# durtest.net
KiCad netlist of a schematic drawn in EAGLE
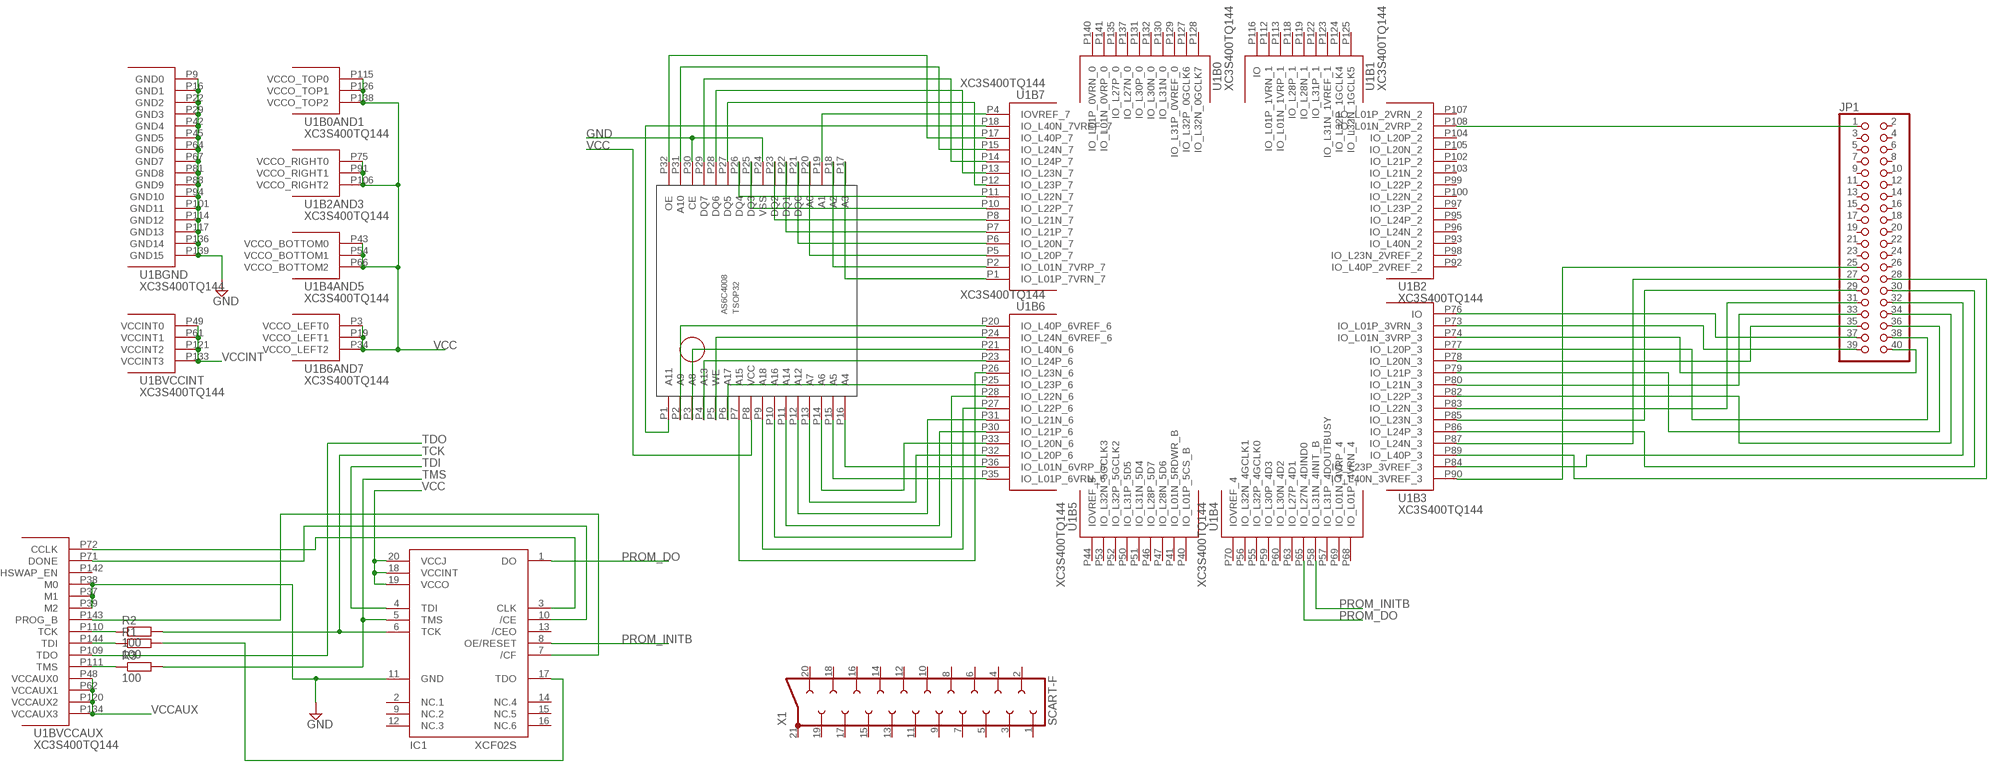
[diagram p0: schematic, sheet 1]

(export (version "E")
  (design (tool "Eeschema 10.0.6"))
  (components
    (comp (ref "IC1")
      (value "XCF02S")
      (footprint "eagle-import:VO20")
      (libsource (lib "eagle-import") (part "XCF02S"))
    )
    (comp (ref "JP1")
      (value "PINHD-2X20")
      (footprint "eagle-import:2X20")
      (libsource (lib "eagle-import") (part "PINHD-2X20"))
    )
    (comp (ref "R1")
      (value "100")
      (footprint "eagle-import:R0805")
      (libsource (lib "eagle-import") (part "R-EU_R0805"))
    )
    (comp (ref "R2")
      (value "100")
      (footprint "eagle-import:R0805")
      (libsource (lib "eagle-import") (part "R-EU_R0805"))
    )
    (comp (ref "R3")
      (value "100")
      (footprint "eagle-import:R0805")
      (libsource (lib "eagle-import") (part "R-EU_R0805"))
    )
    (comp (ref "U$1")
      (value "AS6C4008")
      (footprint "eagle-import:TSOP32")
      (libsource (lib "eagle-import") (part "AS6C4008"))
    )
    (comp (ref "U1")
      (value "XC3S400TQ144")
      (footprint "eagle-import:TQ144")
      (libsource (lib "eagle-import") (part "XC3S400TQ144"))
    )
    (comp (ref "X1")
      (value "SCART-F")
      (footprint "eagle-import:SCART-F")
      (libsource (lib "eagle-import") (part "SCART-F"))
    )
  )
  (nets
    (net (code "1") (name "/PROM_DO") (class "Default")
      (node (ref "IC1") (pin "1") (pinfunction "DO_1") (pintype "bidirectional"))
      (node (ref "U1") (pin "P65") (pinfunction "IO_L27N_4DIND0_P65") (pintype "bidirectional"))
    )
    (net (code "2") (name "/PROM_INITB") (class "Default")
      (node (ref "IC1") (pin "8") (pinfunction "OE/RESET_8") (pintype "bidirectional"))
      (node (ref "U1") (pin "P58") (pinfunction "IO_L31N_4INIT_B_P58") (pintype "bidirectional"))
    )
    (net (code "3") (name "/TCK") (class "Default")
      (node (ref "IC1") (pin "6") (pinfunction "TCK_6") (pintype "bidirectional"))
      (node (ref "R2") (pin "2") (pinfunction "2_2") (pintype "passive"))
    )
    (net (code "4") (name "/TDI") (class "Default")
      (node (ref "IC1") (pin "4") (pinfunction "TDI_4") (pintype "bidirectional"))
    )
    (net (code "5") (name "/TDO") (class "Default")
      (node (ref "U1") (pin "P109") (pinfunction "TDO_P109") (pintype "bidirectional"))
    )
    (net (code "6") (name "/TMS") (class "Default")
      (node (ref "IC1") (pin "5") (pinfunction "TMS_5") (pintype "bidirectional"))
      (node (ref "R3") (pin "2") (pinfunction "2_2") (pintype "passive"))
    )
    (net (code "7") (name "/VCC") (class "Default")
      (node (ref "IC1") (pin "18") (pinfunction "VCCINT_18") (pintype "bidirectional"))
      (node (ref "IC1") (pin "19") (pinfunction "VCCO_19") (pintype "bidirectional"))
      (node (ref "IC1") (pin "20") (pinfunction "VCCJ_20") (pintype "bidirectional"))
      (node (ref "U$1") (pin "P8") (pinfunction "VCC_P8") (pintype "bidirectional"))
      (node (ref "U1") (pin "P106") (pinfunction "VCCO_RIGHT2_P106") (pintype "passive"))
      (node (ref "U1") (pin "P115") (pinfunction "VCCO_TOP0_P115") (pintype "passive"))
      (node (ref "U1") (pin "P126") (pinfunction "VCCO_TOP1_P126") (pintype "passive"))
      (node (ref "U1") (pin "P138") (pinfunction "VCCO_TOP2_P138") (pintype "passive"))
      (node (ref "U1") (pin "P19") (pinfunction "VCCO_LEFT1_P19") (pintype "passive"))
      (node (ref "U1") (pin "P3") (pinfunction "VCCO_LEFT0_P3") (pintype "passive"))
      (node (ref "U1") (pin "P34") (pinfunction "VCCO_LEFT2_P34") (pintype "passive"))
      (node (ref "U1") (pin "P43") (pinfunction "VCCO_BOTTOM0_P43") (pintype "passive"))
      (node (ref "U1") (pin "P54") (pinfunction "VCCO_BOTTOM1_P54") (pintype "passive"))
      (node (ref "U1") (pin "P66") (pinfunction "VCCO_BOTTOM2_P66") (pintype "passive"))
      (node (ref "U1") (pin "P75") (pinfunction "VCCO_RIGHT0_P75") (pintype "passive"))
      (node (ref "U1") (pin "P91") (pinfunction "VCCO_RIGHT1_P91") (pintype "passive"))
    )
    (net (code "8") (name "/VCCAUX") (class "Default")
      (node (ref "U1") (pin "P120") (pinfunction "VCCAUX2_P120") (pintype "passive"))
      (node (ref "U1") (pin "P134") (pinfunction "VCCAUX3_P134") (pintype "passive"))
      (node (ref "U1") (pin "P48") (pinfunction "VCCAUX0_P48") (pintype "passive"))
      (node (ref "U1") (pin "P62") (pinfunction "VCCAUX1_P62") (pintype "passive"))
    )
    (net (code "9") (name "/VCCINT") (class "Default")
      (node (ref "U1") (pin "P121") (pinfunction "VCCINT2_P121") (pintype "passive"))
      (node (ref "U1") (pin "P133") (pinfunction "VCCINT3_P133") (pintype "passive"))
      (node (ref "U1") (pin "P49") (pinfunction "VCCINT0_P49") (pintype "passive"))
      (node (ref "U1") (pin "P61") (pinfunction "VCCINT1_P61") (pintype "passive"))
    )
    (net (code "10") (name "GND") (class "Default")
      (node (ref "IC1") (pin "11") (pinfunction "GND_11") (pintype "bidirectional"))
      (node (ref "U$1") (pin "P24") (pinfunction "VSS_P24") (pintype "bidirectional"))
      (node (ref "U$1") (pin "P30") (pinfunction "CE_P30") (pintype "bidirectional"))
      (node (ref "U1") (pin "P101") (pinfunction "GND11_P101") (pintype "passive"))
      (node (ref "U1") (pin "P114") (pinfunction "GND12_P114") (pintype "passive"))
      (node (ref "U1") (pin "P117") (pinfunction "GND13_P117") (pintype "passive"))
      (node (ref "U1") (pin "P136") (pinfunction "GND14_P136") (pintype "passive"))
      (node (ref "U1") (pin "P139") (pinfunction "GND15_P139") (pintype "passive"))
      (node (ref "U1") (pin "P16") (pinfunction "GND1_P16") (pintype "passive"))
      (node (ref "U1") (pin "P22") (pinfunction "GND2_P22") (pintype "passive"))
      (node (ref "U1") (pin "P29") (pinfunction "GND3_P29") (pintype "passive"))
      (node (ref "U1") (pin "P37") (pinfunction "M1_P37") (pintype "bidirectional"))
      (node (ref "U1") (pin "P38") (pinfunction "M0_P38") (pintype "bidirectional"))
      (node (ref "U1") (pin "P39") (pinfunction "M2_P39") (pintype "bidirectional"))
      (node (ref "U1") (pin "P42") (pinfunction "GND4_P42") (pintype "passive"))
      (node (ref "U1") (pin "P45") (pinfunction "GND5_P45") (pintype "passive"))
      (node (ref "U1") (pin "P64") (pinfunction "GND6_P64") (pintype "passive"))
      (node (ref "U1") (pin "P67") (pinfunction "GND7_P67") (pintype "passive"))
      (node (ref "U1") (pin "P81") (pinfunction "GND8_P81") (pintype "passive"))
      (node (ref "U1") (pin "P88") (pinfunction "GND9_P88") (pintype "passive"))
      (node (ref "U1") (pin "P9") (pinfunction "GND0_P9") (pintype "passive"))
      (node (ref "U1") (pin "P94") (pinfunction "GND10_P94") (pintype "passive"))
    )
    (net (code "11") (name "Net-(IC1-CLK)") (class "Default")
      (node (ref "IC1") (pin "3") (pinfunction "CLK_3") (pintype "bidirectional"))
      (node (ref "U1") (pin "P72") (pinfunction "CCLK_P72") (pintype "bidirectional"))
    )
    (net (code "12") (name "Net-(IC1-TDO)") (class "Default")
      (node (ref "IC1") (pin "17") (pinfunction "TDO_17") (pintype "bidirectional"))
      (node (ref "R1") (pin "2") (pinfunction "2_2") (pintype "passive"))
    )
    (net (code "13") (name "Net-(IC1-{slash}CE)") (class "Default")
      (node (ref "IC1") (pin "10") (pinfunction "/CE_10") (pintype "bidirectional"))
      (node (ref "U1") (pin "P71") (pinfunction "DONE_P71") (pintype "bidirectional"))
    )
    (net (code "14") (name "Net-(IC1-{slash}CF)") (class "Default")
      (node (ref "IC1") (pin "7") (pinfunction "/CF_7") (pintype "bidirectional"))
      (node (ref "U1") (pin "P143") (pinfunction "PROG_B_P143") (pintype "bidirectional"))
    )
    (net (code "15") (name "Net-(U$1-A0)") (class "Default")
      (node (ref "U$1") (pin "P20") (pinfunction "A0_P20") (pintype "bidirectional"))
      (node (ref "U1") (pin "P5") (pinfunction "IO_L20P_7_P5") (pintype "bidirectional"))
    )
    (net (code "16") (name "Net-(U$1-A1)") (class "Default")
      (node (ref "U$1") (pin "P19") (pinfunction "A1_P19") (pintype "bidirectional"))
      (node (ref "U1") (pin "P4") (pinfunction "IOVREF_7_P4") (pintype "bidirectional"))
    )
    (net (code "17") (name "Net-(U$1-A2)") (class "Default")
      (node (ref "U$1") (pin "P18") (pinfunction "A2_P18") (pintype "bidirectional"))
      (node (ref "U1") (pin "P2") (pinfunction "IO_L01N_7VRP_7_P2") (pintype "bidirectional"))
    )
    (net (code "18") (name "Net-(U$1-A3)") (class "Default")
      (node (ref "U$1") (pin "P17") (pinfunction "A3_P17") (pintype "bidirectional"))
      (node (ref "U1") (pin "P1") (pinfunction "IO_L01P_7VRN_7_P1") (pintype "bidirectional"))
    )
    (net (code "19") (name "Net-(U$1-A4)") (class "Default")
      (node (ref "U$1") (pin "P16") (pinfunction "A4_P16") (pintype "bidirectional"))
      (node (ref "U1") (pin "P36") (pinfunction "IO_L01N_6VRP_6_P36") (pintype "bidirectional"))
    )
    (net (code "20") (name "Net-(U$1-A5)") (class "Default")
      (node (ref "U$1") (pin "P15") (pinfunction "A5_P15") (pintype "bidirectional"))
      (node (ref "U1") (pin "P35") (pinfunction "IO_L01P_6VRN_6_P35") (pintype "bidirectional"))
    )
    (net (code "21") (name "Net-(U$1-A6)") (class "Default")
      (node (ref "U$1") (pin "P14") (pinfunction "A6_P14") (pintype "bidirectional"))
      (node (ref "U1") (pin "P33") (pinfunction "IO_L20N_6_P33") (pintype "bidirectional"))
    )
    (net (code "22") (name "Net-(U$1-A7)") (class "Default")
      (node (ref "U$1") (pin "P13") (pinfunction "A7_P13") (pintype "bidirectional"))
      (node (ref "U1") (pin "P32") (pinfunction "IO_L20P_6_P32") (pintype "bidirectional"))
    )
    (net (code "23") (name "Net-(U$1-A8)") (class "Default")
      (node (ref "U$1") (pin "P3") (pinfunction "A8_P3") (pintype "bidirectional"))
      (node (ref "U1") (pin "P21") (pinfunction "IO_L40N_6_P21") (pintype "bidirectional"))
    )
    (net (code "24") (name "Net-(U$1-A9)") (class "Default")
      (node (ref "U$1") (pin "P2") (pinfunction "A9_P2") (pintype "bidirectional"))
      (node (ref "U1") (pin "P20") (pinfunction "IO_L40P_6VREF_6_P20") (pintype "bidirectional"))
    )
    (net (code "25") (name "Net-(U$1-A10)") (class "Default")
      (node (ref "U$1") (pin "P31") (pinfunction "A10_P31") (pintype "bidirectional"))
      (node (ref "U1") (pin "P15") (pinfunction "IO_L24N_7_P15") (pintype "bidirectional"))
    )
    (net (code "26") (name "Net-(U$1-A11)") (class "Default")
      (node (ref "U$1") (pin "P1") (pinfunction "A11_P1") (pintype "bidirectional"))
      (node (ref "U1") (pin "P18") (pinfunction "IO_L40N_7VREF_7_P18") (pintype "bidirectional"))
    )
    (net (code "27") (name "Net-(U$1-A12)") (class "Default")
      (node (ref "U$1") (pin "P12") (pinfunction "A12_P12") (pintype "bidirectional"))
      (node (ref "U1") (pin "P31") (pinfunction "IO_L21N_6_P31") (pintype "bidirectional"))
    )
    (net (code "28") (name "Net-(U$1-A13)") (class "Default")
      (node (ref "U$1") (pin "P4") (pinfunction "A13_P4") (pintype "bidirectional"))
      (node (ref "U1") (pin "P23") (pinfunction "IO_L24P_6_P23") (pintype "bidirectional"))
    )
    (net (code "29") (name "Net-(U$1-A14)") (class "Default")
      (node (ref "U$1") (pin "P11") (pinfunction "A14_P11") (pintype "bidirectional"))
      (node (ref "U1") (pin "P30") (pinfunction "IO_L21P_6_P30") (pintype "bidirectional"))
    )
    (net (code "30") (name "Net-(U$1-A15)") (class "Default")
      (node (ref "U$1") (pin "P7") (pinfunction "A15_P7") (pintype "bidirectional"))
      (node (ref "U1") (pin "P26") (pinfunction "IO_L23N_6_P26") (pintype "bidirectional"))
    )
    (net (code "31") (name "Net-(U$1-A16)") (class "Default")
      (node (ref "U$1") (pin "P10") (pinfunction "A16_P10") (pintype "bidirectional"))
      (node (ref "U1") (pin "P28") (pinfunction "IO_L22N_6_P28") (pintype "bidirectional"))
    )
    (net (code "32") (name "Net-(U$1-A17)") (class "Default")
      (node (ref "U$1") (pin "P6") (pinfunction "A17_P6") (pintype "bidirectional"))
      (node (ref "U1") (pin "P25") (pinfunction "IO_L23P_6_P25") (pintype "bidirectional"))
    )
    (net (code "33") (name "Net-(U$1-A18)") (class "Default")
      (node (ref "U$1") (pin "P9") (pinfunction "A18_P9") (pintype "bidirectional"))
      (node (ref "U1") (pin "P27") (pinfunction "IO_L22P_6_P27") (pintype "bidirectional"))
    )
    (net (code "34") (name "Net-(U$1-DQ0)") (class "Default")
      (node (ref "U$1") (pin "P21") (pinfunction "DQ0_P21") (pintype "bidirectional"))
      (node (ref "U1") (pin "P6") (pinfunction "IO_L20N_7_P6") (pintype "bidirectional"))
    )
    (net (code "35") (name "Net-(U$1-DQ1)") (class "Default")
      (node (ref "U$1") (pin "P22") (pinfunction "DQ1_P22") (pintype "bidirectional"))
      (node (ref "U1") (pin "P7") (pinfunction "IO_L21P_7_P7") (pintype "bidirectional"))
    )
    (net (code "36") (name "Net-(U$1-DQ2)") (class "Default")
      (node (ref "U$1") (pin "P23") (pinfunction "DQ2_P23") (pintype "bidirectional"))
      (node (ref "U1") (pin "P8") (pinfunction "IO_L21N_7_P8") (pintype "bidirectional"))
    )
    (net (code "37") (name "Net-(U$1-DQ3)") (class "Default")
      (node (ref "U$1") (pin "P25") (pinfunction "DQ3_P25") (pintype "bidirectional"))
      (node (ref "U1") (pin "P10") (pinfunction "IO_L22P_7_P10") (pintype "bidirectional"))
    )
    (net (code "38") (name "Net-(U$1-DQ4)") (class "Default")
      (node (ref "U$1") (pin "P26") (pinfunction "DQ4_P26") (pintype "bidirectional"))
      (node (ref "U1") (pin "P11") (pinfunction "IO_L22N_7_P11") (pintype "bidirectional"))
    )
    (net (code "39") (name "Net-(U$1-DQ5)") (class "Default")
      (node (ref "U$1") (pin "P27") (pinfunction "DQ5_P27") (pintype "bidirectional"))
      (node (ref "U1") (pin "P12") (pinfunction "IO_L23P_7_P12") (pintype "bidirectional"))
    )
    (net (code "40") (name "Net-(U$1-DQ6)") (class "Default")
      (node (ref "U$1") (pin "P28") (pinfunction "DQ6_P28") (pintype "bidirectional"))
      (node (ref "U1") (pin "P13") (pinfunction "IO_L23N_7_P13") (pintype "bidirectional"))
    )
    (net (code "41") (name "Net-(U$1-DQ7)") (class "Default")
      (node (ref "U$1") (pin "P29") (pinfunction "DQ7_P29") (pintype "bidirectional"))
      (node (ref "U1") (pin "P14") (pinfunction "IO_L24P_7_P14") (pintype "bidirectional"))
    )
    (net (code "42") (name "Net-(U$1-OE)") (class "Default")
      (node (ref "U$1") (pin "P32") (pinfunction "OE_P32") (pintype "bidirectional"))
      (node (ref "U1") (pin "P17") (pinfunction "IO_L40P_7_P17") (pintype "bidirectional"))
    )
    (net (code "43") (name "Net-(U$1-WE)") (class "Default")
      (node (ref "U$1") (pin "P5") (pinfunction "WE_P5") (pintype "bidirectional"))
      (node (ref "U1") (pin "P24") (pinfunction "IO_L24N_6VREF_6_P24") (pintype "bidirectional"))
    )
    (net (code "44") (name "Net-(U1D-IO_L01N_2VRP_2)") (class "Default")
      (node (ref "JP1") (pin "1") (pinfunction "1_1") (pintype "passive"))
      (node (ref "U1") (pin "P108") (pinfunction "IO_L01N_2VRP_2_P108") (pintype "bidirectional"))
    )
    (net (code "45") (name "Net-(U1F-IO)") (class "Default")
      (node (ref "JP1") (pin "37") (pinfunction "37_37") (pintype "passive"))
      (node (ref "U1") (pin "P76") (pinfunction "IO_P76") (pintype "bidirectional"))
    )
    (net (code "46") (name "Net-(U1F-IO_L01N_3VRP_3)") (class "Default")
      (node (ref "JP1") (pin "40") (pinfunction "40_40") (pintype "passive"))
      (node (ref "U1") (pin "P74") (pinfunction "IO_L01N_3VRP_3_P74") (pintype "bidirectional"))
    )
    (net (code "47") (name "Net-(U1F-IO_L01P_3VRN_3)") (class "Default")
      (node (ref "JP1") (pin "39") (pinfunction "39_39") (pintype "passive"))
      (node (ref "U1") (pin "P73") (pinfunction "IO_L01P_3VRN_3_P73") (pintype "bidirectional"))
    )
    (net (code "48") (name "Net-(U1F-IO_L20N_3)") (class "Default")
      (node (ref "JP1") (pin "35") (pinfunction "35_35") (pintype "passive"))
      (node (ref "U1") (pin "P78") (pinfunction "IO_L20N_3_P78") (pintype "bidirectional"))
    )
    (net (code "49") (name "Net-(U1F-IO_L20P_3)") (class "Default")
      (node (ref "JP1") (pin "38") (pinfunction "38_38") (pintype "passive"))
      (node (ref "U1") (pin "P77") (pinfunction "IO_L20P_3_P77") (pintype "bidirectional"))
    )
    (net (code "50") (name "Net-(U1F-IO_L21N_3)") (class "Default")
      (node (ref "JP1") (pin "33") (pinfunction "33_33") (pintype "passive"))
      (node (ref "U1") (pin "P80") (pinfunction "IO_L21N_3_P80") (pintype "bidirectional"))
    )
    (net (code "51") (name "Net-(U1F-IO_L21P_3)") (class "Default")
      (node (ref "JP1") (pin "36") (pinfunction "36_36") (pintype "passive"))
      (node (ref "U1") (pin "P79") (pinfunction "IO_L21P_3_P79") (pintype "bidirectional"))
    )
    (net (code "52") (name "Net-(U1F-IO_L22N_3)") (class "Default")
      (node (ref "JP1") (pin "31") (pinfunction "31_31") (pintype "passive"))
      (node (ref "U1") (pin "P83") (pinfunction "IO_L22N_3_P83") (pintype "bidirectional"))
    )
    (net (code "53") (name "Net-(U1F-IO_L22P_3)") (class "Default")
      (node (ref "JP1") (pin "34") (pinfunction "34_34") (pintype "passive"))
      (node (ref "U1") (pin "P82") (pinfunction "IO_L22P_3_P82") (pintype "bidirectional"))
    )
    (net (code "54") (name "Net-(U1F-IO_L23N_3)") (class "Default")
      (node (ref "JP1") (pin "29") (pinfunction "29_29") (pintype "passive"))
      (node (ref "U1") (pin "P85") (pinfunction "IO_L23N_3_P85") (pintype "bidirectional"))
    )
    (net (code "55") (name "Net-(U1F-IO_L23P_3VREF_3)") (class "Default")
      (node (ref "JP1") (pin "32") (pinfunction "32_32") (pintype "passive"))
      (node (ref "U1") (pin "P84") (pinfunction "IO_L23P_3VREF_3_P84") (pintype "bidirectional"))
    )
    (net (code "56") (name "Net-(U1F-IO_L24N_3)") (class "Default")
      (node (ref "JP1") (pin "27") (pinfunction "27_27") (pintype "passive"))
      (node (ref "U1") (pin "P87") (pinfunction "IO_L24N_3_P87") (pintype "bidirectional"))
    )
    (net (code "57") (name "Net-(U1F-IO_L24P_3)") (class "Default")
      (node (ref "JP1") (pin "30") (pinfunction "30_30") (pintype "passive"))
      (node (ref "U1") (pin "P86") (pinfunction "IO_L24P_3_P86") (pintype "bidirectional"))
    )
    (net (code "58") (name "Net-(U1F-IO_L40N_3VREF_3)") (class "Default")
      (node (ref "JP1") (pin "25") (pinfunction "25_25") (pintype "passive"))
      (node (ref "U1") (pin "P90") (pinfunction "IO_L40N_3VREF_3_P90") (pintype "bidirectional"))
    )
    (net (code "59") (name "Net-(U1F-IO_L40P_3)") (class "Default")
      (node (ref "JP1") (pin "28") (pinfunction "28_28") (pintype "passive"))
      (node (ref "U1") (pin "P89") (pinfunction "IO_L40P_3_P89") (pintype "bidirectional"))
    )
    (net (code "60") (name "Net-(U1N-TCK)") (class "Default")
      (node (ref "R2") (pin "1") (pinfunction "1_1") (pintype "passive"))
      (node (ref "U1") (pin "P110") (pinfunction "TCK_P110") (pintype "bidirectional"))
    )
    (net (code "61") (name "Net-(U1N-TDI)") (class "Default")
      (node (ref "R1") (pin "1") (pinfunction "1_1") (pintype "passive"))
      (node (ref "U1") (pin "P144") (pinfunction "TDI_P144") (pintype "bidirectional"))
    )
    (net (code "62") (name "Net-(U1N-TMS)") (class "Default")
      (node (ref "R3") (pin "1") (pinfunction "1_1") (pintype "passive"))
      (node (ref "U1") (pin "P111") (pinfunction "TMS_P111") (pintype "bidirectional"))
    )
    (net (code "63") (name "unconnected-(IC1-NC.1-Pad2)") (class "Default")
      (node (ref "IC1") (pin "2") (pinfunction "NC.1_2") (pintype "bidirectional"))
    )
    (net (code "64") (name "unconnected-(IC1-NC.2-Pad9)") (class "Default")
      (node (ref "IC1") (pin "9") (pinfunction "NC.2_9") (pintype "bidirectional"))
    )
    (net (code "65") (name "unconnected-(IC1-NC.3-Pad12)") (class "Default")
      (node (ref "IC1") (pin "12") (pinfunction "NC.3_12") (pintype "bidirectional"))
    )
    (net (code "66") (name "unconnected-(IC1-NC.4-Pad14)") (class "Default")
      (node (ref "IC1") (pin "14") (pinfunction "NC.4_14") (pintype "bidirectional"))
    )
    (net (code "67") (name "unconnected-(IC1-NC.5-Pad15)") (class "Default")
      (node (ref "IC1") (pin "15") (pinfunction "NC.5_15") (pintype "bidirectional"))
    )
    (net (code "68") (name "unconnected-(IC1-NC.6-Pad16)") (class "Default")
      (node (ref "IC1") (pin "16") (pinfunction "NC.6_16") (pintype "bidirectional"))
    )
    (net (code "69") (name "unconnected-(IC1-{slash}CEO-Pad13)") (class "Default")
      (node (ref "IC1") (pin "13") (pinfunction "/CEO_13") (pintype "bidirectional"))
    )
    (net (code "70") (name "unconnected-(JP1-Pad2)") (class "Default")
      (node (ref "JP1") (pin "2") (pinfunction "2_2") (pintype "passive"))
    )
    (net (code "71") (name "unconnected-(JP1-Pad3)") (class "Default")
      (node (ref "JP1") (pin "3") (pinfunction "3_3") (pintype "passive"))
    )
    (net (code "72") (name "unconnected-(JP1-Pad4)") (class "Default")
      (node (ref "JP1") (pin "4") (pinfunction "4_4") (pintype "passive"))
    )
    (net (code "73") (name "unconnected-(JP1-Pad5)") (class "Default")
      (node (ref "JP1") (pin "5") (pinfunction "5_5") (pintype "passive"))
    )
    (net (code "74") (name "unconnected-(JP1-Pad6)") (class "Default")
      (node (ref "JP1") (pin "6") (pinfunction "6_6") (pintype "passive"))
    )
    (net (code "75") (name "unconnected-(JP1-Pad7)") (class "Default")
      (node (ref "JP1") (pin "7") (pinfunction "7_7") (pintype "passive"))
    )
    (net (code "76") (name "unconnected-(JP1-Pad8)") (class "Default")
      (node (ref "JP1") (pin "8") (pinfunction "8_8") (pintype "passive"))
    )
    (net (code "77") (name "unconnected-(JP1-Pad9)") (class "Default")
      (node (ref "JP1") (pin "9") (pinfunction "9_9") (pintype "passive"))
    )
    (net (code "78") (name "unconnected-(JP1-Pad10)") (class "Default")
      (node (ref "JP1") (pin "10") (pinfunction "10_10") (pintype "passive"))
    )
    (net (code "79") (name "unconnected-(JP1-Pad11)") (class "Default")
      (node (ref "JP1") (pin "11") (pinfunction "11_11") (pintype "passive"))
    )
    (net (code "80") (name "unconnected-(JP1-Pad12)") (class "Default")
      (node (ref "JP1") (pin "12") (pinfunction "12_12") (pintype "passive"))
    )
    (net (code "81") (name "unconnected-(JP1-Pad13)") (class "Default")
      (node (ref "JP1") (pin "13") (pinfunction "13_13") (pintype "passive"))
    )
    (net (code "82") (name "unconnected-(JP1-Pad14)") (class "Default")
      (node (ref "JP1") (pin "14") (pinfunction "14_14") (pintype "passive"))
    )
    (net (code "83") (name "unconnected-(JP1-Pad15)") (class "Default")
      (node (ref "JP1") (pin "15") (pinfunction "15_15") (pintype "passive"))
    )
    (net (code "84") (name "unconnected-(JP1-Pad16)") (class "Default")
      (node (ref "JP1") (pin "16") (pinfunction "16_16") (pintype "passive"))
    )
    (net (code "85") (name "unconnected-(JP1-Pad17)") (class "Default")
      (node (ref "JP1") (pin "17") (pinfunction "17_17") (pintype "passive"))
    )
    (net (code "86") (name "unconnected-(JP1-Pad18)") (class "Default")
      (node (ref "JP1") (pin "18") (pinfunction "18_18") (pintype "passive"))
    )
    (net (code "87") (name "unconnected-(JP1-Pad19)") (class "Default")
      (node (ref "JP1") (pin "19") (pinfunction "19_19") (pintype "passive"))
    )
    (net (code "88") (name "unconnected-(JP1-Pad20)") (class "Default")
      (node (ref "JP1") (pin "20") (pinfunction "20_20") (pintype "passive"))
    )
    (net (code "89") (name "unconnected-(JP1-Pad21)") (class "Default")
      (node (ref "JP1") (pin "21") (pinfunction "21_21") (pintype "passive"))
    )
    (net (code "90") (name "unconnected-(JP1-Pad22)") (class "Default")
      (node (ref "JP1") (pin "22") (pinfunction "22_22") (pintype "passive"))
    )
    (net (code "91") (name "unconnected-(JP1-Pad23)") (class "Default")
      (node (ref "JP1") (pin "23") (pinfunction "23_23") (pintype "passive"))
    )
    (net (code "92") (name "unconnected-(JP1-Pad24)") (class "Default")
      (node (ref "JP1") (pin "24") (pinfunction "24_24") (pintype "passive"))
    )
    (net (code "93") (name "unconnected-(JP1-Pad26)") (class "Default")
      (node (ref "JP1") (pin "26") (pinfunction "26_26") (pintype "passive"))
    )
    (net (code "94") (name "unconnected-(U1A-IO_L01N_0VRP_0-PadP141)") (class "Default")
      (node (ref "U1") (pin "P141") (pinfunction "IO_L01N_0VRP_0_P141") (pintype "bidirectional"))
    )
    (net (code "95") (name "unconnected-(U1A-IO_L01P_0VRN_0-PadP140)") (class "Default")
      (node (ref "U1") (pin "P140") (pinfunction "IO_L01P_0VRN_0_P140") (pintype "bidirectional"))
    )
    (net (code "96") (name "unconnected-(U1A-IO_L27N_0-PadP137)") (class "Default")
      (node (ref "U1") (pin "P137") (pinfunction "IO_L27N_0_P137") (pintype "bidirectional"))
    )
    (net (code "97") (name "unconnected-(U1A-IO_L27P_0-PadP135)") (class "Default")
      (node (ref "U1") (pin "P135") (pinfunction "IO_L27P_0_P135") (pintype "bidirectional"))
    )
    (net (code "98") (name "unconnected-(U1A-IO_L30N_0-PadP132)") (class "Default")
      (node (ref "U1") (pin "P132") (pinfunction "IO_L30N_0_P132") (pintype "bidirectional"))
    )
    (net (code "99") (name "unconnected-(U1A-IO_L30P_0-PadP131)") (class "Default")
      (node (ref "U1") (pin "P131") (pinfunction "IO_L30P_0_P131") (pintype "bidirectional"))
    )
    (net (code "100") (name "unconnected-(U1A-IO_L31N_0-PadP130)") (class "Default")
      (node (ref "U1") (pin "P130") (pinfunction "IO_L31N_0_P130") (pintype "bidirectional"))
    )
    (net (code "101") (name "unconnected-(U1A-IO_L31P_0VREF_0-PadP129)") (class "Default")
      (node (ref "U1") (pin "P129") (pinfunction "IO_L31P_0VREF_0_P129") (pintype "bidirectional"))
    )
    (net (code "102") (name "unconnected-(U1A-IO_L32N_0GCLK7-PadP128)") (class "Default")
      (node (ref "U1") (pin "P128") (pinfunction "IO_L32N_0GCLK7_P128") (pintype "bidirectional"))
    )
    (net (code "103") (name "unconnected-(U1A-IO_L32P_0GCLK6-PadP127)") (class "Default")
      (node (ref "U1") (pin "P127") (pinfunction "IO_L32P_0GCLK6_P127") (pintype "bidirectional"))
    )
    (net (code "104") (name "unconnected-(U1C-IO-PadP116)") (class "Default")
      (node (ref "U1") (pin "P116") (pinfunction "IO_P116") (pintype "bidirectional"))
    )
    (net (code "105") (name "unconnected-(U1C-IO_L01N_1VRP_1-PadP113)") (class "Default")
      (node (ref "U1") (pin "P113") (pinfunction "IO_L01N_1VRP_1_P113") (pintype "bidirectional"))
    )
    (net (code "106") (name "unconnected-(U1C-IO_L01P_1VRN_1-PadP112)") (class "Default")
      (node (ref "U1") (pin "P112") (pinfunction "IO_L01P_1VRN_1_P112") (pintype "bidirectional"))
    )
    (net (code "107") (name "unconnected-(U1C-IO_L28N_1-PadP119)") (class "Default")
      (node (ref "U1") (pin "P119") (pinfunction "IO_L28N_1_P119") (pintype "bidirectional"))
    )
    (net (code "108") (name "unconnected-(U1C-IO_L28P_1-PadP118)") (class "Default")
      (node (ref "U1") (pin "P118") (pinfunction "IO_L28P_1_P118") (pintype "bidirectional"))
    )
    (net (code "109") (name "unconnected-(U1C-IO_L31N_1VREF_1-PadP123)") (class "Default")
      (node (ref "U1") (pin "P123") (pinfunction "IO_L31N_1VREF_1_P123") (pintype "bidirectional"))
    )
    (net (code "110") (name "unconnected-(U1C-IO_L31P_1-PadP122)") (class "Default")
      (node (ref "U1") (pin "P122") (pinfunction "IO_L31P_1_P122") (pintype "bidirectional"))
    )
    (net (code "111") (name "unconnected-(U1C-IO_L32N_1GCLK5-PadP125)") (class "Default")
      (node (ref "U1") (pin "P125") (pinfunction "IO_L32N_1GCLK5_P125") (pintype "bidirectional"))
    )
    (net (code "112") (name "unconnected-(U1C-IO_L32P_1GCLK4-PadP124)") (class "Default")
      (node (ref "U1") (pin "P124") (pinfunction "IO_L32P_1GCLK4_P124") (pintype "bidirectional"))
    )
    (net (code "113") (name "unconnected-(U1D-IO_L01P_2VRN_2-PadP107)") (class "Default")
      (node (ref "U1") (pin "P107") (pinfunction "IO_L01P_2VRN_2_P107") (pintype "bidirectional"))
    )
    (net (code "114") (name "unconnected-(U1D-IO_L20N_2-PadP105)") (class "Default")
      (node (ref "U1") (pin "P105") (pinfunction "IO_L20N_2_P105") (pintype "bidirectional"))
    )
    (net (code "115") (name "unconnected-(U1D-IO_L20P_2-PadP104)") (class "Default")
      (node (ref "U1") (pin "P104") (pinfunction "IO_L20P_2_P104") (pintype "bidirectional"))
    )
    (net (code "116") (name "unconnected-(U1D-IO_L21N_2-PadP103)") (class "Default")
      (node (ref "U1") (pin "P103") (pinfunction "IO_L21N_2_P103") (pintype "bidirectional"))
    )
    (net (code "117") (name "unconnected-(U1D-IO_L21P_2-PadP102)") (class "Default")
      (node (ref "U1") (pin "P102") (pinfunction "IO_L21P_2_P102") (pintype "bidirectional"))
    )
    (net (code "118") (name "unconnected-(U1D-IO_L22N_2-PadP100)") (class "Default")
      (node (ref "U1") (pin "P100") (pinfunction "IO_L22N_2_P100") (pintype "bidirectional"))
    )
    (net (code "119") (name "unconnected-(U1D-IO_L22P_2-PadP99)") (class "Default")
      (node (ref "U1") (pin "P99") (pinfunction "IO_L22P_2_P99") (pintype "bidirectional"))
    )
    (net (code "120") (name "unconnected-(U1D-IO_L23N_2VREF_2-PadP98)") (class "Default")
      (node (ref "U1") (pin "P98") (pinfunction "IO_L23N_2VREF_2_P98") (pintype "bidirectional"))
    )
    (net (code "121") (name "unconnected-(U1D-IO_L23P_2-PadP97)") (class "Default")
      (node (ref "U1") (pin "P97") (pinfunction "IO_L23P_2_P97") (pintype "bidirectional"))
    )
    (net (code "122") (name "unconnected-(U1D-IO_L24N_2-PadP96)") (class "Default")
      (node (ref "U1") (pin "P96") (pinfunction "IO_L24N_2_P96") (pintype "bidirectional"))
    )
    (net (code "123") (name "unconnected-(U1D-IO_L24P_2-PadP95)") (class "Default")
      (node (ref "U1") (pin "P95") (pinfunction "IO_L24P_2_P95") (pintype "bidirectional"))
    )
    (net (code "124") (name "unconnected-(U1D-IO_L40N_2-PadP93)") (class "Default")
      (node (ref "U1") (pin "P93") (pinfunction "IO_L40N_2_P93") (pintype "bidirectional"))
    )
    (net (code "125") (name "unconnected-(U1D-IO_L40P_2VREF_2-PadP92)") (class "Default")
      (node (ref "U1") (pin "P92") (pinfunction "IO_L40P_2VREF_2_P92") (pintype "bidirectional"))
    )
    (net (code "126") (name "unconnected-(U1G-IOVREF_4-PadP70)") (class "Default")
      (node (ref "U1") (pin "P70") (pinfunction "IOVREF_4_P70") (pintype "bidirectional"))
    )
    (net (code "127") (name "unconnected-(U1G-IO_L01N_4VRP_4-PadP69)") (class "Default")
      (node (ref "U1") (pin "P69") (pinfunction "IO_L01N_4VRP_4_P69") (pintype "bidirectional"))
    )
    (net (code "128") (name "unconnected-(U1G-IO_L01P_4VRN_4-PadP68)") (class "Default")
      (node (ref "U1") (pin "P68") (pinfunction "IO_L01P_4VRN_4_P68") (pintype "bidirectional"))
    )
    (net (code "129") (name "unconnected-(U1G-IO_L27P_4D1-PadP63)") (class "Default")
      (node (ref "U1") (pin "P63") (pinfunction "IO_L27P_4D1_P63") (pintype "bidirectional"))
    )
    (net (code "130") (name "unconnected-(U1G-IO_L30N_4D2-PadP60)") (class "Default")
      (node (ref "U1") (pin "P60") (pinfunction "IO_L30N_4D2_P60") (pintype "bidirectional"))
    )
    (net (code "131") (name "unconnected-(U1G-IO_L30P_4D3-PadP59)") (class "Default")
      (node (ref "U1") (pin "P59") (pinfunction "IO_L30P_4D3_P59") (pintype "bidirectional"))
    )
    (net (code "132") (name "unconnected-(U1G-IO_L31P_4DOUTBUSY-PadP57)") (class "Default")
      (node (ref "U1") (pin "P57") (pinfunction "IO_L31P_4DOUTBUSY_P57") (pintype "bidirectional"))
    )
    (net (code "133") (name "unconnected-(U1G-IO_L32N_4GCLK1-PadP56)") (class "Default")
      (node (ref "U1") (pin "P56") (pinfunction "IO_L32N_4GCLK1_P56") (pintype "bidirectional"))
    )
    (net (code "134") (name "unconnected-(U1G-IO_L32P_4GCLK0-PadP55)") (class "Default")
      (node (ref "U1") (pin "P55") (pinfunction "IO_L32P_4GCLK0_P55") (pintype "bidirectional"))
    )
    (net (code "135") (name "unconnected-(U1I-IOVREF_5-PadP44)") (class "Default")
      (node (ref "U1") (pin "P44") (pinfunction "IOVREF_5_P44") (pintype "bidirectional"))
    )
    (net (code "136") (name "unconnected-(U1I-IO_L01N_5RDWR_B-PadP41)") (class "Default")
      (node (ref "U1") (pin "P41") (pinfunction "IO_L01N_5RDWR_B_P41") (pintype "bidirectional"))
    )
    (net (code "137") (name "unconnected-(U1I-IO_L01P_5CS_B-PadP40)") (class "Default")
      (node (ref "U1") (pin "P40") (pinfunction "IO_L01P_5CS_B_P40") (pintype "bidirectional"))
    )
    (net (code "138") (name "unconnected-(U1I-IO_L28N_5D6-PadP47)") (class "Default")
      (node (ref "U1") (pin "P47") (pinfunction "IO_L28N_5D6_P47") (pintype "bidirectional"))
    )
    (net (code "139") (name "unconnected-(U1I-IO_L28P_5D7-PadP46)") (class "Default")
      (node (ref "U1") (pin "P46") (pinfunction "IO_L28P_5D7_P46") (pintype "bidirectional"))
    )
    (net (code "140") (name "unconnected-(U1I-IO_L31N_5D4-PadP51)") (class "Default")
      (node (ref "U1") (pin "P51") (pinfunction "IO_L31N_5D4_P51") (pintype "bidirectional"))
    )
    (net (code "141") (name "unconnected-(U1I-IO_L31P_5D5-PadP50)") (class "Default")
      (node (ref "U1") (pin "P50") (pinfunction "IO_L31P_5D5_P50") (pintype "bidirectional"))
    )
    (net (code "142") (name "unconnected-(U1I-IO_L32N_5GCLK3-PadP53)") (class "Default")
      (node (ref "U1") (pin "P53") (pinfunction "IO_L32N_5GCLK3_P53") (pintype "bidirectional"))
    )
    (net (code "143") (name "unconnected-(U1I-IO_L32P_5GCLK2-PadP52)") (class "Default")
      (node (ref "U1") (pin "P52") (pinfunction "IO_L32P_5GCLK2_P52") (pintype "bidirectional"))
    )
    (net (code "144") (name "unconnected-(U1N-HSWAP_EN-PadP142)") (class "Default")
      (node (ref "U1") (pin "P142") (pinfunction "HSWAP_EN_P142") (pintype "bidirectional"))
    )
    (net (code "145") (name "unconnected-(X1-Pad1)") (class "Default")
      (node (ref "X1") (pin "1") (pinfunction "1_1") (pintype "passive"))
    )
    (net (code "146") (name "unconnected-(X1-Pad2)") (class "Default")
      (node (ref "X1") (pin "2") (pinfunction "2_2") (pintype "passive"))
    )
    (net (code "147") (name "unconnected-(X1-Pad3)") (class "Default")
      (node (ref "X1") (pin "3") (pinfunction "3_3") (pintype "passive"))
    )
    (net (code "148") (name "unconnected-(X1-Pad4)") (class "Default")
      (node (ref "X1") (pin "4") (pinfunction "4_4") (pintype "passive"))
    )
    (net (code "149") (name "unconnected-(X1-Pad5)") (class "Default")
      (node (ref "X1") (pin "5") (pinfunction "5_5") (pintype "passive"))
    )
    (net (code "150") (name "unconnected-(X1-Pad6)") (class "Default")
      (node (ref "X1") (pin "6") (pinfunction "6_6") (pintype "passive"))
    )
    (net (code "151") (name "unconnected-(X1-Pad7)") (class "Default")
      (node (ref "X1") (pin "7") (pinfunction "7_7") (pintype "passive"))
    )
    (net (code "152") (name "unconnected-(X1-Pad8)") (class "Default")
      (node (ref "X1") (pin "8") (pinfunction "8_8") (pintype "passive"))
    )
    (net (code "153") (name "unconnected-(X1-Pad9)") (class "Default")
      (node (ref "X1") (pin "9") (pinfunction "9_9") (pintype "passive"))
    )
    (net (code "154") (name "unconnected-(X1-Pad10)") (class "Default")
      (node (ref "X1") (pin "10") (pinfunction "10_10") (pintype "passive"))
    )
    (net (code "155") (name "unconnected-(X1-Pad11)") (class "Default")
      (node (ref "X1") (pin "11") (pinfunction "11_11") (pintype "passive"))
    )
    (net (code "156") (name "unconnected-(X1-Pad12)") (class "Default")
      (node (ref "X1") (pin "12") (pinfunction "12_12") (pintype "passive"))
    )
    (net (code "157") (name "unconnected-(X1-Pad13)") (class "Default")
      (node (ref "X1") (pin "13") (pinfunction "13_13") (pintype "passive"))
    )
    (net (code "158") (name "unconnected-(X1-Pad14)") (class "Default")
      (node (ref "X1") (pin "14") (pinfunction "14_14") (pintype "passive"))
    )
    (net (code "159") (name "unconnected-(X1-Pad15)") (class "Default")
      (node (ref "X1") (pin "15") (pinfunction "15_15") (pintype "passive"))
    )
    (net (code "160") (name "unconnected-(X1-Pad16)") (class "Default")
      (node (ref "X1") (pin "16") (pinfunction "16_16") (pintype "passive"))
    )
    (net (code "161") (name "unconnected-(X1-Pad17)") (class "Default")
      (node (ref "X1") (pin "17") (pinfunction "17_17") (pintype "passive"))
    )
    (net (code "162") (name "unconnected-(X1-Pad18)") (class "Default")
      (node (ref "X1") (pin "18") (pinfunction "18_18") (pintype "passive"))
    )
    (net (code "163") (name "unconnected-(X1-Pad19)") (class "Default")
      (node (ref "X1") (pin "19") (pinfunction "19_19") (pintype "passive"))
    )
    (net (code "164") (name "unconnected-(X1-Pad20)") (class "Default")
      (node (ref "X1") (pin "20") (pinfunction "20_20") (pintype "passive"))
    )
    (net (code "165") (name "unconnected-(X1-Pad21)") (class "Default")
      (node (ref "X1") (pin "21") (pinfunction "21_21") (pintype "passive"))
    )
  )
)
